# filter_diff_shunt.net
KiCad netlist of a schematic drawn in Altium Designer
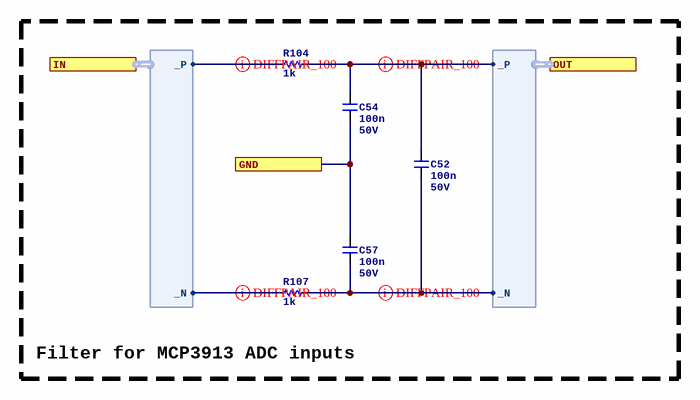
[diagram p0: filter_diff_shunt.SchDoc]

(export (version "E")
  (design (tool "Eeschema 10.0.6"))
  (components
    (comp (ref "C52")
      (value "CL05B104KB54PNC")
      (footprint "C0402")
      (fields
        (field (name "CAPACITANCE") "100n")
        (field (name "MANUFACTURER") "Samsung Electro-Mechanics")
        (field (name "VOLTAGE RATING") "50V")
      )
      (libsource (lib "database") (part "__template_cap"))
    )
    (comp (ref "C54")
      (value "CL05B104KB54PNC")
      (footprint "C0402")
      (fields
        (field (name "CAPACITANCE") "100n")
        (field (name "MANUFACTURER") "Samsung Electro-Mechanics")
        (field (name "VOLTAGE RATING") "50V")
      )
      (libsource (lib "database") (part "__template_cap"))
    )
    (comp (ref "C57")
      (value "CL05B104KB54PNC")
      (footprint "C0402")
      (fields
        (field (name "CAPACITANCE") "100n")
        (field (name "MANUFACTURER") "Samsung Electro-Mechanics")
        (field (name "VOLTAGE RATING") "50V")
      )
      (libsource (lib "database") (part "__template_cap"))
    )
    (comp (ref "R104")
      (value "1k")
      (footprint "R0402")
      (fields
        (field (name "TOLERANCE") "1%")
        (field (name "MANUFACTURER PART NUMBER") "0402WGF1001TCE")
        (field (name "MANUFACTURER") "UNI-ROYAL(Uniroyal Elec)")
      )
      (libsource (lib "database") (part "__template_resistor"))
    )
    (comp (ref "R107")
      (value "1k")
      (footprint "R0402")
      (fields
        (field (name "TOLERANCE") "1%")
        (field (name "MANUFACTURER PART NUMBER") "0402WGF1001TCE")
        (field (name "MANUFACTURER") "UNI-ROYAL(Uniroyal Elec)")
      )
      (libsource (lib "database") (part "__template_resistor"))
    )
  )
  (nets
    (net (code "2") (name "/GND") (class "Default")
      (node (ref "C54") (pin "2") (pintype "passive"))
      (node (ref "C57") (pin "1") (pintype "passive"))
    )
    (net (code "4") (name "Net-(C52-Pad1)") (class "Default")
      (node (ref "C52") (pin "1") (pintype "passive"))
      (node (ref "C54") (pin "1") (pintype "passive"))
      (node (ref "R104") (pin "1") (pintype "passive"))
    )
    (net (code "5") (name "Net-(C52-Pad2)") (class "Default")
      (node (ref "C52") (pin "2") (pintype "passive"))
      (node (ref "C57") (pin "2") (pintype "passive"))
      (node (ref "R107") (pin "1") (pintype "passive"))
    )
    (net (code "6") (name "unconnected-(R104-Pad2)") (class "Default")
      (node (ref "R104") (pin "2") (pintype "passive"))
    )
    (net (code "7") (name "unconnected-(R107-Pad2)") (class "Default")
      (node (ref "R107") (pin "2") (pintype "passive"))
    )
  )
)
